# SCH_5Vdc_1Adc_power_supply_circuit_2024-.net
KiCad netlist of a schematic drawn in EasyEDA
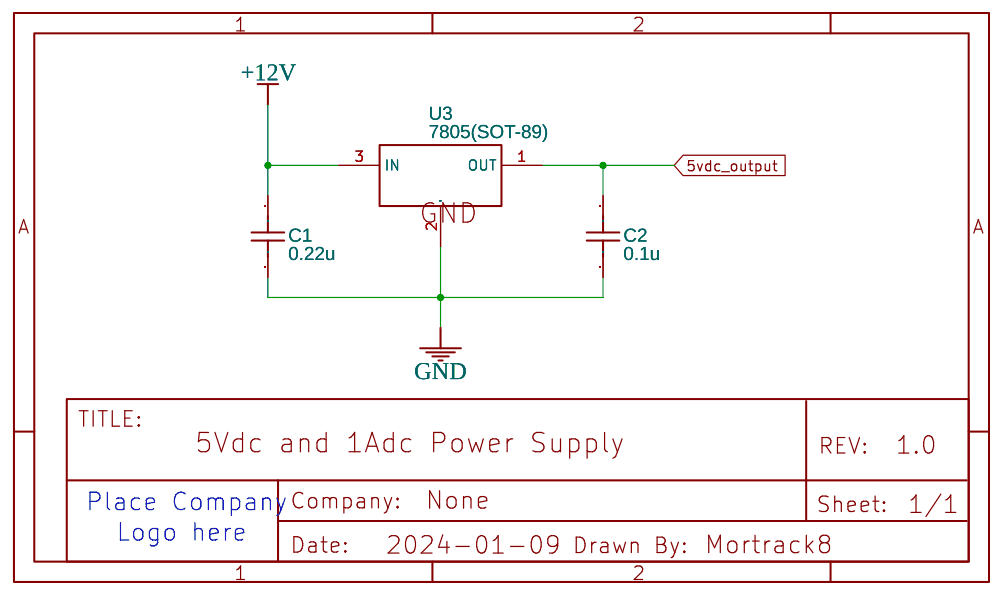
[diagram p0: schematic sheet]

(export (version "E")
  (design (tool "Eeschema 10.0.6"))
  (components
    (comp (ref "C1") (value "0.22u") (libsource (lib "") (part "C_RAD-0.3_US")))
    (comp (ref "C2") (value "0.1u") (libsource (lib "") (part "C_RAD-0.3_US")))
    (comp (ref "U3")
      (value "7805(SOT-89)")
      (fields (field (name "Manufacturer Part") "CJ78L05") (field (name "Manufacturer") "CJ"))
      (libsource (lib "") (part "7805(SOT-89)"))
    )
  )
  (nets
    (net (code "1") (name "+12V") (class "Default")
      (node (ref "C1") (pin "1") (pinfunction "1_1") (pintype "unspecified"))
      (node (ref "U3") (pin "3") (pinfunction "IN_3") (pintype "passive"))
    )
    (net (code "2") (name "5vdc_output") (class "Default")
      (node (ref "C2") (pin "1") (pinfunction "1_1") (pintype "unspecified"))
      (node (ref "U3") (pin "1") (pinfunction "OUT_1") (pintype "passive"))
    )
    (net (code "3") (name "GND") (class "Default")
      (node (ref "C1") (pin "2") (pinfunction "2_2") (pintype "unspecified"))
      (node (ref "C2") (pin "2") (pinfunction "2_2") (pintype "unspecified"))
      (node (ref "U3") (pin "2") (pinfunction "GND_2") (pintype "passive"))
    )
  )
)
